# Sheet1.net
KiCad netlist of a schematic drawn in Altium Designer
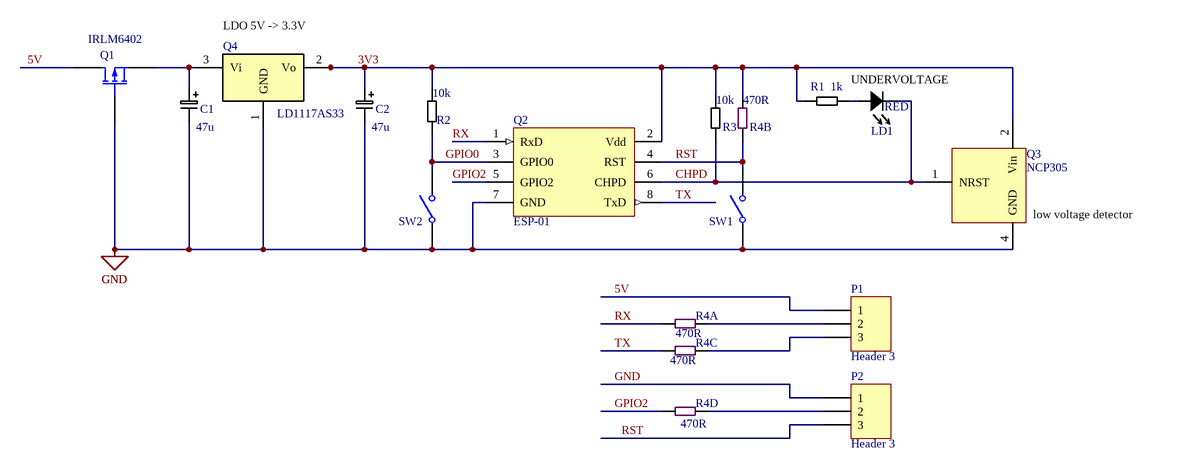
[diagram p0: Sheet1.SchDoc]

(export (version "E")
  (design (tool "Eeschema 10.0.6"))
  (components
    (comp (ref "C1") (value "47u") (footprint "CPol_B") (libsource (lib "ABU_standard") (part "C_EL")))
    (comp (ref "C2") (value "47u") (footprint "CPol_B") (libsource (lib "ABU_standard") (part "C_EL")))
    (comp (ref "LD1") (value "RED") (footprint "LED_SMD") (libsource (lib "ABU_standard") (part "LED")))
    (comp (ref "P1")
      (value "Header 3")
      (footprint "PIN_1x3_SPARSE")
      (description "Header, 3-Pin")
      (fields (field (name "PUBLISHER") "Altium Limited"))
      (libsource (lib "Miscellaneous Connectors") (part "Header 3"))
    )
    (comp (ref "P2")
      (value "Header 3")
      (footprint "PIN_1x3_SPARSE")
      (description "Header, 3-Pin")
      (fields (field (name "PUBLISHER") "Altium Limited"))
      (libsource (lib "Miscellaneous Connectors") (part "Header 3"))
    )
    (comp (ref "Q1")
      (value "IRLM6402")
      (footprint "SOT23")
      (description "P-Channel Enhancement Mode Vertical DMOS FET")
      (libsource (lib "ABU_standard") (part "BSS84"))
    )
    (comp (ref "Q2")
      (value "ESP-01")
      (footprint "ESP_01")
      (description "ESP-01 in socket")
      (libsource (lib "CUSTOM") (part "ESP_01"))
    )
    (comp (ref "Q3")
      (value "NCP305")
      (footprint "SC-82")
      (description "Voltage Watchdog")
      (libsource (lib "CUSTOM") (part "NCP305"))
    )
    (comp (ref "Q4")
      (value "LD1117AS33")
      (footprint "SOT-223/DSO-G3/D6.7")
      (description "Low drop fixed and adjustable positive voltage regulators")
      (fields (field (name "Comment") "LD1117A"))
      (libsource (lib "ABU_standard") (part "LD1117A"))
    )
    (comp (ref "R1") (value "1k") (footprint "R0805") (libsource (lib "") (part "R_1")))
    (comp (ref "R2") (value "10k") (footprint "R0805") (libsource (lib "ABU_standard") (part "R")))
    (comp (ref "R3") (value "10k") (footprint "R0805") (libsource (lib "ABU_standard") (part "R")))
    (comp (ref "R4") (value "470R") (footprint "R1206_Array_longpad") (libsource (lib "") (part "R_ARRAY_1")))
    (comp (ref "SW1") (value "SW") (footprint "TURTLE_BTN") (libsource (lib "CUSTOM") (part "SW_SPST_4PAD")))
    (comp (ref "SW2") (value "SW") (footprint "TURTLE_BTN") (libsource (lib "CUSTOM") (part "SW_SPST_4PAD")))
  )
  (nets
    (net (code "1") (name "/3V3") (class "Default")
      (node (ref "C2") (pin "1") (pinfunction "1_1") (pintype "passive"))
      (node (ref "Q2") (pin "2") (pinfunction "Vdd_2") (pintype "power_in"))
      (node (ref "Q3") (pin "2") (pinfunction "Vin_2") (pintype "power_in"))
      (node (ref "Q4") (pin "2") (pinfunction "Vo_2") (pintype "passive"))
      (node (ref "Q4") (pin "4") (pinfunction "Vo_4") (pintype "passive"))
      (node (ref "R1") (pin "2") (pinfunction "2_2") (pintype "passive"))
      (node (ref "R2") (pin "1") (pinfunction "1_1") (pintype "passive"))
      (node (ref "R3") (pin "1") (pinfunction "1_1") (pintype "passive"))
      (node (ref "R4") (pin "4") (pinfunction "1_4") (pintype "passive"))
    )
    (net (code "2") (name "/5V") (class "Default")
      (node (ref "P1") (pin "1") (pinfunction "1_1") (pintype "passive"))
      (node (ref "Q1") (pin "3") (pinfunction "D_3") (pintype "passive"))
    )
    (net (code "3") (name "/CHPD") (class "Default")
      (node (ref "LD1") (pin "C") (pinfunction "C_C") (pintype "passive"))
      (node (ref "Q2") (pin "6") (pinfunction "CHPD_6") (pintype "passive"))
      (node (ref "Q3") (pin "1") (pinfunction "NRST_1") (pintype "open_collector"))
      (node (ref "R3") (pin "2") (pinfunction "2_2") (pintype "passive"))
    )
    (net (code "4") (name "/GPIO0") (class "Default")
      (node (ref "Q2") (pin "3") (pinfunction "GPIO0_3") (pintype "passive"))
      (node (ref "R2") (pin "2") (pinfunction "2_2") (pintype "passive"))
      (node (ref "SW2") (pin "2") (pinfunction "NO_2") (pintype "passive"))
    )
    (net (code "5") (name "/GPIO2") (class "Default")
      (node (ref "Q2") (pin "5") (pinfunction "GPIO2_5") (pintype "passive"))
      (node (ref "R4") (pin "7") (pinfunction "2_7") (pintype "passive"))
    )
    (net (code "6") (name "/RST") (class "Default")
      (node (ref "P2") (pin "3") (pinfunction "3_3") (pintype "passive"))
      (node (ref "Q2") (pin "4") (pinfunction "RST_4") (pintype "passive"))
      (node (ref "R4") (pin "3") (pinfunction "2_3") (pintype "passive"))
      (node (ref "SW1") (pin "2") (pinfunction "NO_2") (pintype "passive"))
    )
    (net (code "7") (name "/RX") (class "Default")
      (node (ref "Q2") (pin "1") (pinfunction "RxD_1") (pintype "input"))
      (node (ref "R4") (pin "1") (pinfunction "1_1") (pintype "passive"))
    )
    (net (code "8") (name "/TX") (class "Default")
      (node (ref "Q2") (pin "8") (pinfunction "TxD_8") (pintype "output"))
      (node (ref "R4") (pin "5") (pinfunction "2_5") (pintype "passive"))
    )
    (net (code "9") (name "GND") (class "Default")
      (node (ref "C1") (pin "2") (pinfunction "2_2") (pintype "passive"))
      (node (ref "C2") (pin "2") (pinfunction "2_2") (pintype "passive"))
      (node (ref "P2") (pin "1") (pinfunction "1_1") (pintype "passive"))
      (node (ref "Q1") (pin "1") (pinfunction "G_1") (pintype "passive"))
      (node (ref "Q2") (pin "7") (pinfunction "GND_7") (pintype "power_in"))
      (node (ref "Q3") (pin "4") (pinfunction "GND_4") (pintype "power_in"))
      (node (ref "Q4") (pin "1") (pinfunction "GND_1") (pintype "passive"))
      (node (ref "SW1") (pin "1") (pinfunction "COMMON_1") (pintype "passive"))
      (node (ref "SW2") (pin "1") (pinfunction "COMMON_1") (pintype "passive"))
    )
    (net (code "10") (name "Net-(LD1-PadA)") (class "Default")
      (node (ref "LD1") (pin "A") (pinfunction "A_A") (pintype "passive"))
      (node (ref "R1") (pin "1") (pinfunction "1_1") (pintype "passive"))
    )
    (net (code "11") (name "Net-(P1-Pad2)") (class "Default")
      (node (ref "P1") (pin "2") (pinfunction "2_2") (pintype "passive"))
      (node (ref "R4") (pin "2") (pinfunction "2_2") (pintype "passive"))
    )
    (net (code "12") (name "Net-(Q1-S)") (class "Default")
      (node (ref "C1") (pin "1") (pinfunction "1_1") (pintype "passive"))
      (node (ref "Q1") (pin "2") (pinfunction "S_2") (pintype "passive"))
      (node (ref "Q4") (pin "3") (pinfunction "Vi_3") (pintype "passive"))
    )
    (net (code "13") (name "Net-(R4C-1)") (class "Default")
      (node (ref "P1") (pin "3") (pinfunction "3_3") (pintype "passive"))
      (node (ref "R4") (pin "6") (pinfunction "1_6") (pintype "passive"))
    )
    (net (code "14") (name "Net-(R4D-1)") (class "Default")
      (node (ref "P2") (pin "2") (pinfunction "2_2") (pintype "passive"))
      (node (ref "R4") (pin "8") (pinfunction "1_8") (pintype "passive"))
    )
    (net (code "15") (name "unconnected-(Q3-NC-Pad3)") (class "Default")
      (node (ref "Q3") (pin "3") (pinfunction "NC_3") (pintype "passive"))
    )
  )
)
